# D18_1_1.net
KiCad netlist of a schematic drawn in EAGLE
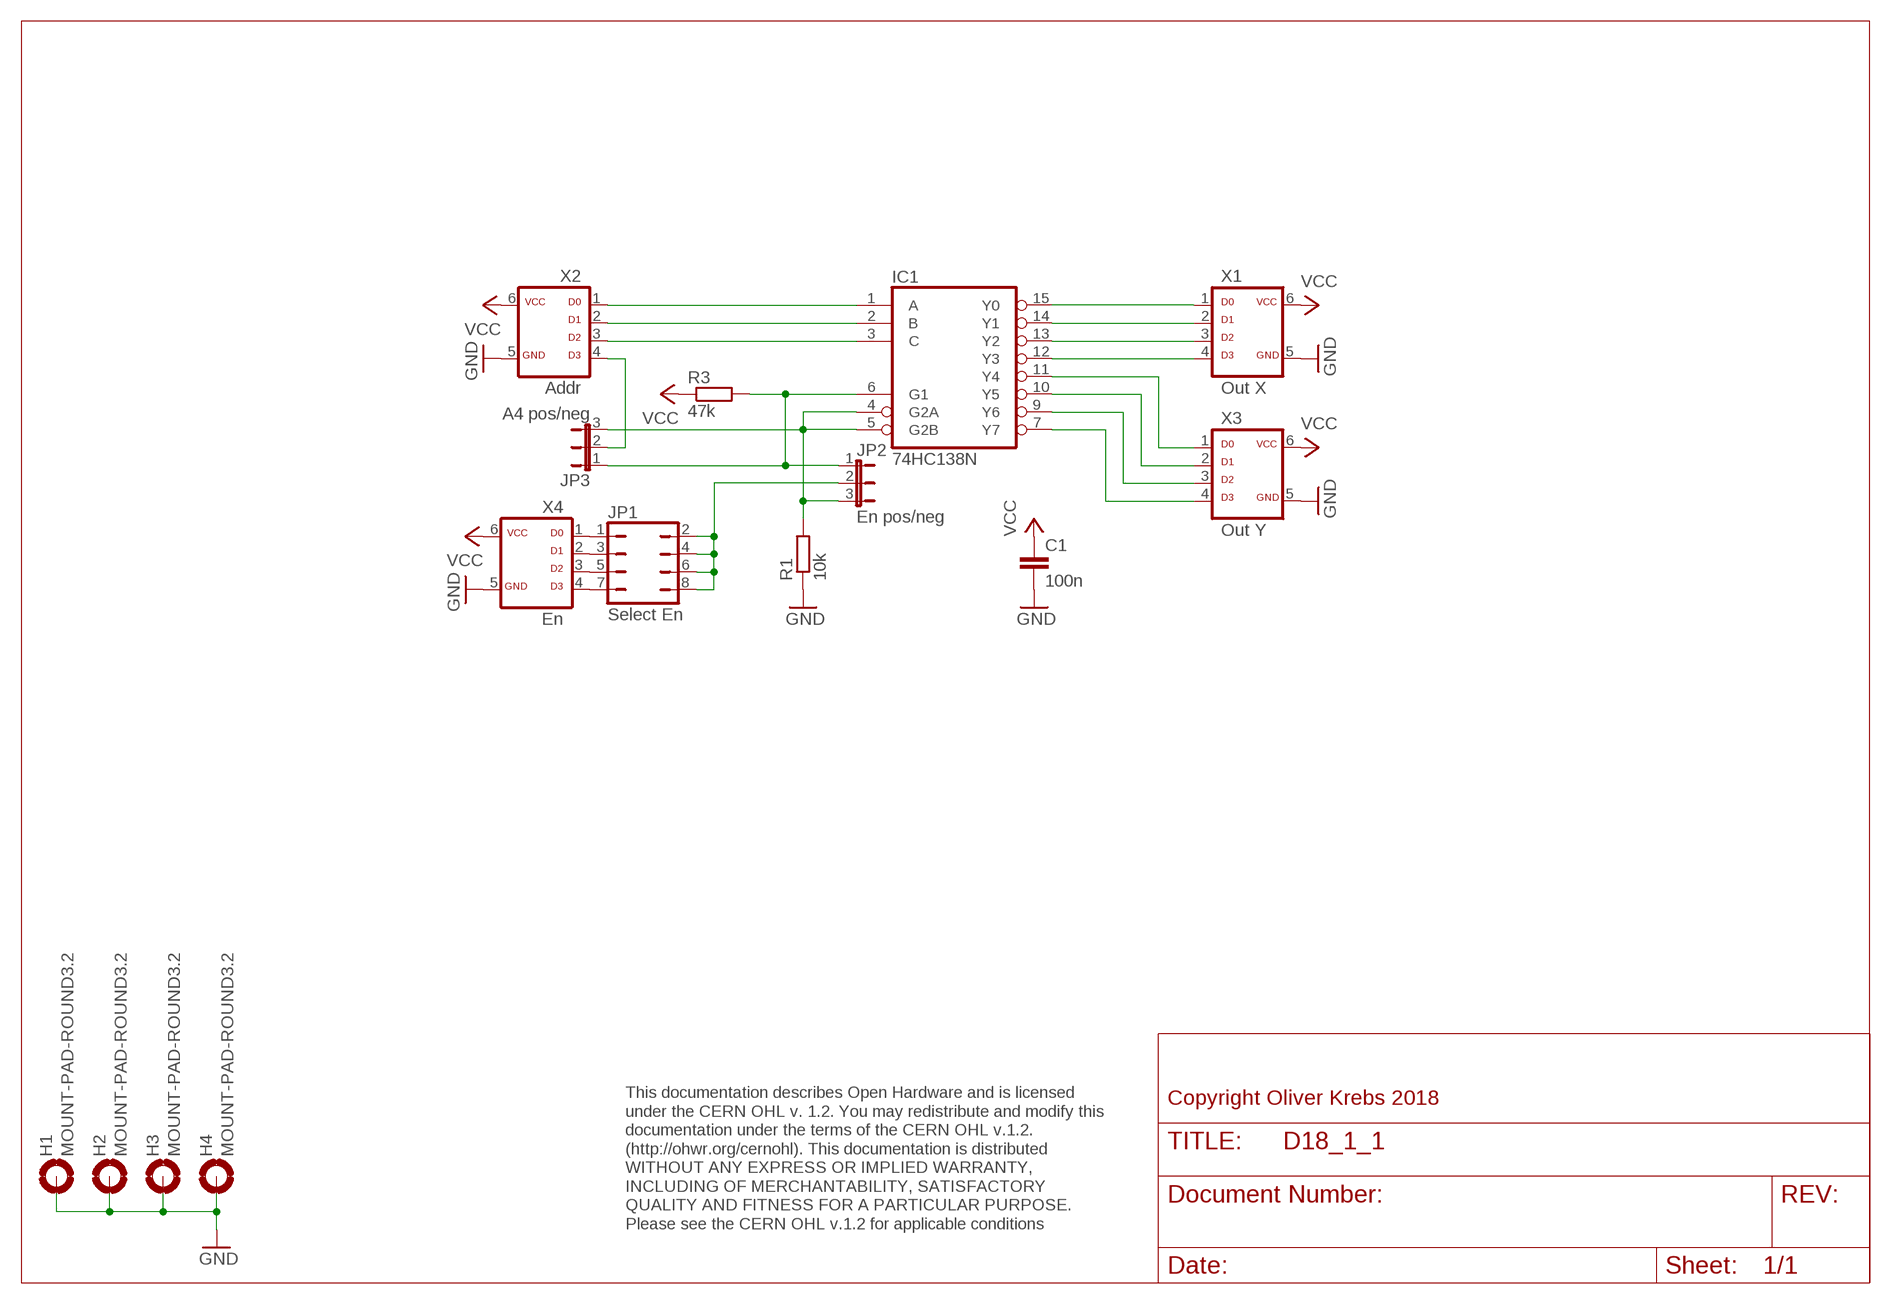
[diagram p0: schematic, sheet 1]

(export (version "E")
  (design (tool "Eeschema 10.0.6"))
  (components
    (comp (ref "C1")
      (value "100n")
      (footprint "eagle-import:C050-025X075")
      (libsource (lib "eagle-import") (part "C-EU050-025X075"))
    )
    (comp (ref "H1")
      (value "MOUNT-PAD-ROUND3.2")
      (footprint "eagle-import:3,2-PAD")
      (libsource (lib "eagle-import") (part "MOUNT-PAD-ROUND3.2"))
    )
    (comp (ref "H2")
      (value "MOUNT-PAD-ROUND3.2")
      (footprint "eagle-import:3,2-PAD")
      (libsource (lib "eagle-import") (part "MOUNT-PAD-ROUND3.2"))
    )
    (comp (ref "H3")
      (value "MOUNT-PAD-ROUND3.2")
      (footprint "eagle-import:3,2-PAD")
      (libsource (lib "eagle-import") (part "MOUNT-PAD-ROUND3.2"))
    )
    (comp (ref "H4")
      (value "MOUNT-PAD-ROUND3.2")
      (footprint "eagle-import:3,2-PAD")
      (libsource (lib "eagle-import") (part "MOUNT-PAD-ROUND3.2"))
    )
    (comp (ref "IC1")
      (value "74HC138N")
      (footprint "eagle-import:DIL16")
      (libsource (lib "eagle-import") (part "74138NHC"))
    )
    (comp (ref "JP1")
      (value "Select En")
      (footprint "eagle-import:JP4Q")
      (libsource (lib "eagle-import") (part "JP4Q"))
    )
    (comp (ref "JP2")
      (value "En pos/neg")
      (footprint "eagle-import:JP2-U")
      (libsource (lib "eagle-import") (part "JP2EJP2-U"))
    )
    (comp (ref "JP3")
      (value "A4 pos/neg")
      (footprint "eagle-import:JP2-U")
      (libsource (lib "eagle-import") (part "JP2EJP2-U"))
    )
    (comp (ref "R1")
      (value "10k")
      (footprint "eagle-import:0207_10")
      (libsource (lib "eagle-import") (part "R-EU_0207/10"))
    )
    (comp (ref "R3")
      (value "47k")
      (footprint "eagle-import:0207_10")
      (libsource (lib "eagle-import") (part "R-EU_0207/10"))
    )
    (comp (ref "X1")
      (value "Out X")
      (footprint "eagle-import:ML-6")
      (libsource (lib "eagle-import") (part "ML6D"))
    )
    (comp (ref "X2")
      (value "Addr")
      (footprint "eagle-import:ML-6")
      (libsource (lib "eagle-import") (part "ML6D"))
    )
    (comp (ref "X3")
      (value "Out Y")
      (footprint "eagle-import:ML-6")
      (libsource (lib "eagle-import") (part "ML6D"))
    )
    (comp (ref "X4")
      (value "En")
      (footprint "eagle-import:ML-6")
      (libsource (lib "eagle-import") (part "ML6D"))
    )
  )
  (nets
    (net (code "1") (name "GND") (class "Default")
      (node (ref "C1") (pin "2") (pinfunction "2_2") (pintype "passive"))
      (node (ref "H1") (pin "B3,2") (pinfunction "MOUNT_B3,2") (pintype "passive"))
      (node (ref "H2") (pin "B3,2") (pinfunction "MOUNT_B3,2") (pintype "passive"))
      (node (ref "H3") (pin "B3,2") (pinfunction "MOUNT_B3,2") (pintype "passive"))
      (node (ref "H4") (pin "B3,2") (pinfunction "MOUNT_B3,2") (pintype "passive"))
      (node (ref "R1") (pin "1") (pinfunction "1_1") (pintype "passive"))
      (node (ref "X1") (pin "5") (pinfunction "5_5") (pintype "passive"))
      (node (ref "X2") (pin "5") (pinfunction "5_5") (pintype "passive"))
      (node (ref "X3") (pin "5") (pinfunction "5_5") (pintype "passive"))
      (node (ref "X4") (pin "5") (pinfunction "5_5") (pintype "passive"))
    )
    (net (code "2") (name "Net-(IC1A-A)") (class "Default")
      (node (ref "IC1") (pin "1") (pinfunction "A_1") (pintype "input"))
      (node (ref "X2") (pin "1") (pinfunction "1_1") (pintype "passive"))
    )
    (net (code "3") (name "Net-(IC1A-B)") (class "Default")
      (node (ref "IC1") (pin "2") (pinfunction "B_2") (pintype "input"))
      (node (ref "X2") (pin "2") (pinfunction "2_2") (pintype "passive"))
    )
    (net (code "4") (name "Net-(IC1A-C)") (class "Default")
      (node (ref "IC1") (pin "3") (pinfunction "C_3") (pintype "input"))
      (node (ref "X2") (pin "3") (pinfunction "3_3") (pintype "passive"))
    )
    (net (code "5") (name "Net-(IC1A-G1)") (class "Default")
      (node (ref "IC1") (pin "6") (pinfunction "G1_6") (pintype "input"))
      (node (ref "JP2") (pin "1") (pinfunction "1_1") (pintype "passive"))
      (node (ref "JP3") (pin "1") (pinfunction "1_1") (pintype "passive"))
      (node (ref "R3") (pin "2") (pinfunction "2_2") (pintype "passive"))
    )
    (net (code "6") (name "Net-(IC1A-G2A)") (class "Default")
      (node (ref "IC1") (pin "4") (pinfunction "G2A_4") (pintype "input"))
      (node (ref "IC1") (pin "5") (pinfunction "G2B_5") (pintype "input"))
      (node (ref "JP2") (pin "3") (pinfunction "3_3") (pintype "passive"))
      (node (ref "JP3") (pin "3") (pinfunction "3_3") (pintype "passive"))
      (node (ref "R1") (pin "2") (pinfunction "2_2") (pintype "passive"))
    )
    (net (code "7") (name "Net-(IC1A-Y0)") (class "Default")
      (node (ref "IC1") (pin "15") (pinfunction "Y0_15") (pintype "output"))
      (node (ref "X1") (pin "1") (pinfunction "1_1") (pintype "passive"))
    )
    (net (code "8") (name "Net-(IC1A-Y1)") (class "Default")
      (node (ref "IC1") (pin "14") (pinfunction "Y1_14") (pintype "output"))
      (node (ref "X1") (pin "2") (pinfunction "2_2") (pintype "passive"))
    )
    (net (code "9") (name "Net-(IC1A-Y2)") (class "Default")
      (node (ref "IC1") (pin "13") (pinfunction "Y2_13") (pintype "output"))
      (node (ref "X1") (pin "3") (pinfunction "3_3") (pintype "passive"))
    )
    (net (code "10") (name "Net-(IC1A-Y3)") (class "Default")
      (node (ref "IC1") (pin "12") (pinfunction "Y3_12") (pintype "output"))
      (node (ref "X1") (pin "4") (pinfunction "4_4") (pintype "passive"))
    )
    (net (code "11") (name "Net-(IC1A-Y4)") (class "Default")
      (node (ref "IC1") (pin "11") (pinfunction "Y4_11") (pintype "output"))
      (node (ref "X3") (pin "1") (pinfunction "1_1") (pintype "passive"))
    )
    (net (code "12") (name "Net-(IC1A-Y5)") (class "Default")
      (node (ref "IC1") (pin "10") (pinfunction "Y5_10") (pintype "output"))
      (node (ref "X3") (pin "2") (pinfunction "2_2") (pintype "passive"))
    )
    (net (code "13") (name "Net-(IC1A-Y6)") (class "Default")
      (node (ref "IC1") (pin "9") (pinfunction "Y6_9") (pintype "output"))
      (node (ref "X3") (pin "3") (pinfunction "3_3") (pintype "passive"))
    )
    (net (code "14") (name "Net-(IC1A-Y7)") (class "Default")
      (node (ref "IC1") (pin "7") (pinfunction "Y7_7") (pintype "output"))
      (node (ref "X3") (pin "4") (pinfunction "4_4") (pintype "passive"))
    )
    (net (code "15") (name "Net-(JP1-Pad1)") (class "Default")
      (node (ref "JP1") (pin "1") (pinfunction "1_1") (pintype "passive"))
      (node (ref "X4") (pin "1") (pinfunction "1_1") (pintype "passive"))
    )
    (net (code "16") (name "Net-(JP1-Pad2)") (class "Default")
      (node (ref "JP1") (pin "2") (pinfunction "2_2") (pintype "passive"))
      (node (ref "JP1") (pin "4") (pinfunction "4_4") (pintype "passive"))
      (node (ref "JP1") (pin "6") (pinfunction "6_6") (pintype "passive"))
      (node (ref "JP1") (pin "8") (pinfunction "8_8") (pintype "passive"))
      (node (ref "JP2") (pin "2") (pinfunction "2_2") (pintype "passive"))
    )
    (net (code "17") (name "Net-(JP1-Pad3)") (class "Default")
      (node (ref "JP1") (pin "3") (pinfunction "3_3") (pintype "passive"))
      (node (ref "X4") (pin "2") (pinfunction "2_2") (pintype "passive"))
    )
    (net (code "18") (name "Net-(JP1-Pad5)") (class "Default")
      (node (ref "JP1") (pin "5") (pinfunction "5_5") (pintype "passive"))
      (node (ref "X4") (pin "3") (pinfunction "3_3") (pintype "passive"))
    )
    (net (code "19") (name "Net-(JP1-Pad7)") (class "Default")
      (node (ref "JP1") (pin "7") (pinfunction "7_7") (pintype "passive"))
      (node (ref "X4") (pin "4") (pinfunction "4_4") (pintype "passive"))
    )
    (net (code "20") (name "Net-(JP3-Pad2)") (class "Default")
      (node (ref "JP3") (pin "2") (pinfunction "2_2") (pintype "passive"))
      (node (ref "X2") (pin "4") (pinfunction "4_4") (pintype "passive"))
    )
    (net (code "21") (name "VCC") (class "Default")
      (node (ref "C1") (pin "1") (pinfunction "1_1") (pintype "passive"))
      (node (ref "R3") (pin "1") (pinfunction "1_1") (pintype "passive"))
      (node (ref "X1") (pin "6") (pinfunction "6_6") (pintype "passive"))
      (node (ref "X2") (pin "6") (pinfunction "6_6") (pintype "passive"))
      (node (ref "X3") (pin "6") (pinfunction "6_6") (pintype "passive"))
      (node (ref "X4") (pin "6") (pinfunction "6_6") (pintype "passive"))
    )
  )
)
